# 220ACTo5VDC6AUSB_E3.net
KiCad netlist of a schematic drawn in Altium Designer
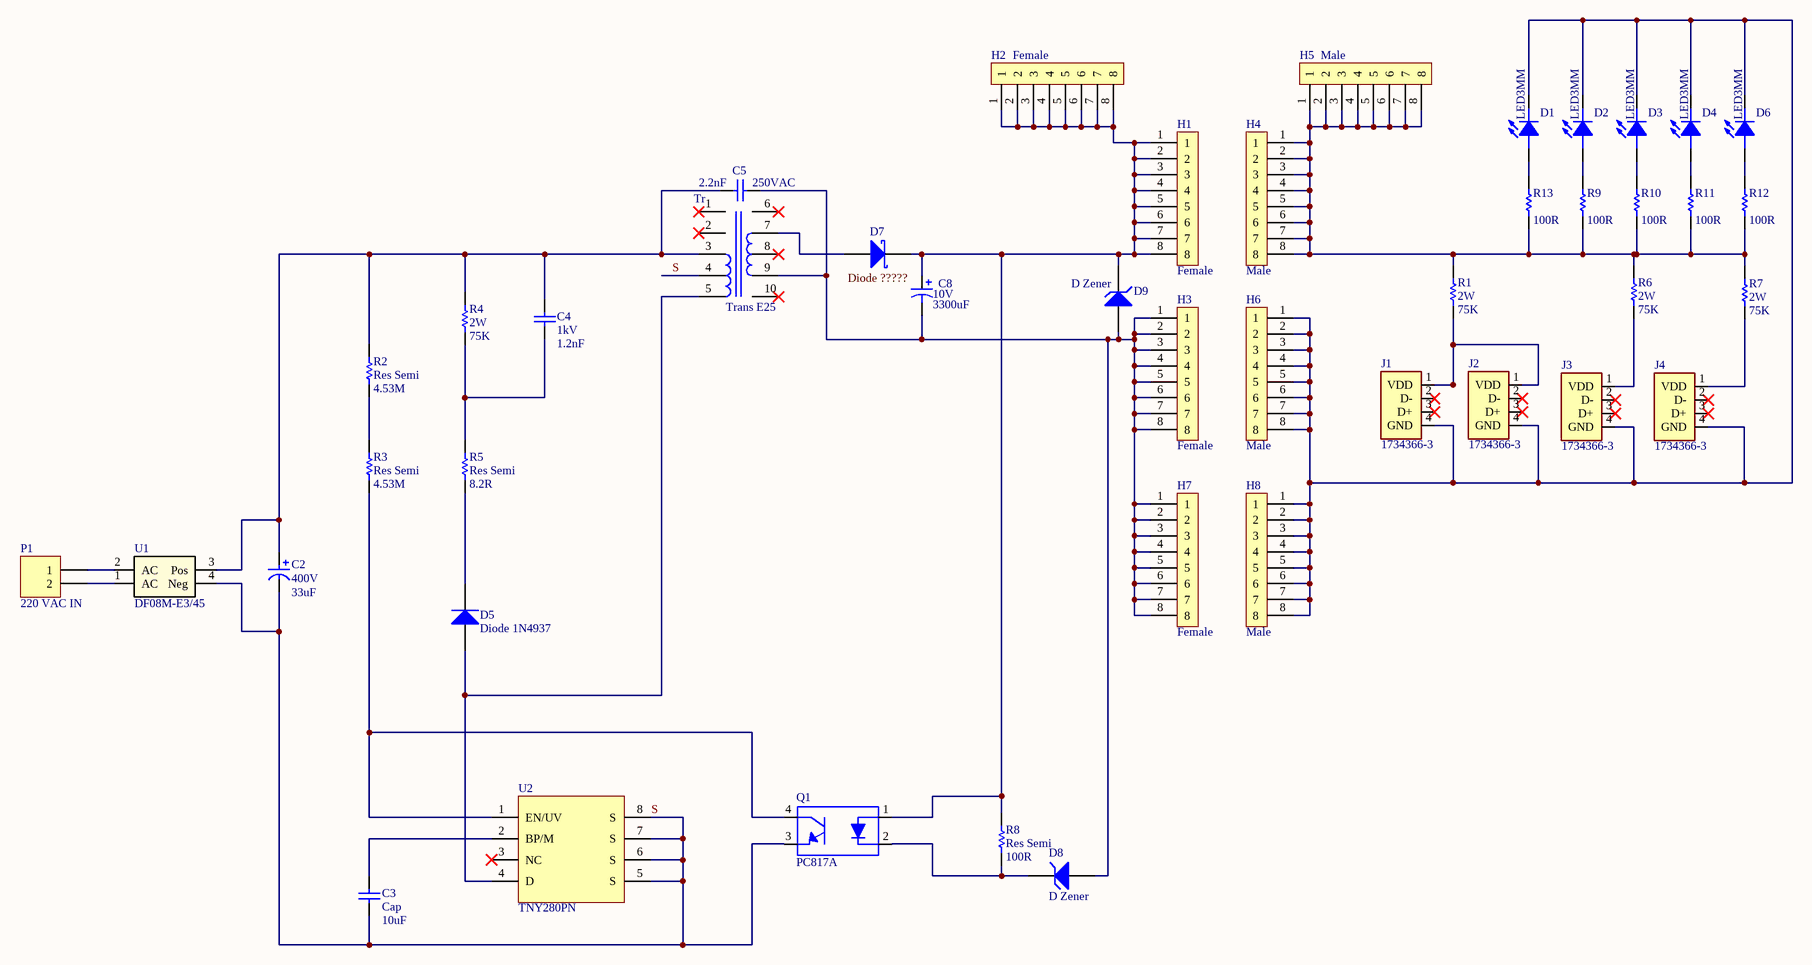
[diagram p0: 220ACTo5VDC6AUSB_E3.SchDoc]

(export (version "E")
  (design (tool "Eeschema 10.0.6"))
  (components
    (comp (ref "C2")
      (value "400V")
      (footprint "RB7.6_15_400v33uf - duplicate")
      (description "Polarized Capacitor (Radial)")
      (fields (field (name "ALTIUM_VALUE") "33uF") (field (name "PUBLISHER") "Altium Limited"))
      (libsource (lib "AC_DC_USB") (part "Cap Pol1"))
    )
    (comp (ref "C3")
      (value "Cap")
      (footprint "RAD-0.3_Ceramic_CAP")
      (description "Capacitor")
      (fields (field (name "16V") "10uF") (field (name "PUBLISHER") "Altium Limited"))
      (libsource (lib "Miscellaneous Devices") (part "Cap"))
    )
    (comp (ref "C4")
      (value "1kV")
      (footprint "RAD-0.3_Ceramic_CAP")
      (description "Capacitor")
      (fields (field (name "1KV") "1.2nF") (field (name "PUBLISHER") "Altium Limited"))
      (libsource (lib "Miscellaneous Devices") (part "Cap"))
    )
    (comp (ref "C5")
      (value "250VAC")
      (footprint "RAD-0.3_Ceramic_CAP")
      (description "Capacitor")
      (fields (field (name "250V") "2.2nF") (field (name "PUBLISHER") "Altium Limited"))
      (libsource (lib "Miscellaneous Devices") (part "Cap"))
    )
    (comp (ref "C8")
      (value "10V")
      (footprint "RB7.6_15_400v33uf")
      (description "Polarized Capacitor (Radial)")
      (fields (field (name "ALTIUM_VALUE") "3300uF") (field (name "PUBLISHER") "Altium Limited"))
      (libsource (lib "Miscellaneous Devices") (part "Cap Pol1"))
    )
    (comp (ref "D1")
      (value "LED3MM")
      (footprint "LED3mm_GREEN")
      (description "Light Emitting Diode")
      (fields (field (name "DESIGNER") "Ali Hafizi"))
      (libsource (lib "AC_DC_USB") (part "LED 3MM"))
    )
    (comp (ref "D2")
      (value "LED3MM")
      (footprint "LED3mm_GREEN")
      (description "Light Emitting Diode")
      (fields (field (name "DESIGNER") "Ali Hafizi"))
      (libsource (lib "AC_DC_USB") (part "LED 3MM"))
    )
    (comp (ref "D3")
      (value "LED3MM")
      (footprint "LED3mm_GREEN")
      (description "Light Emitting Diode")
      (fields (field (name "DESIGNER") "Ali Hafizi"))
      (libsource (lib "AC_DC_USB") (part "LED 3MM"))
    )
    (comp (ref "D4")
      (value "LED3MM")
      (footprint "LED3mm_GREEN")
      (description "Light Emitting Diode")
      (fields (field (name "DESIGNER") "Ali Hafizi"))
      (libsource (lib "AC_DC_USB") (part "LED 3MM"))
    )
    (comp (ref "D5")
      (value "Diode 1N4937")
      (footprint "DO-41_1N4006")
      (description "1 Amp General Purpose Rectifier")
      (fields (field (name "PUBLISHER") "Altium Limited"))
      (libsource (lib "Miscellaneous Devices") (part "Diode 1N4001"))
    )
    (comp (ref "D6")
      (value "LED3MM")
      (footprint "LED3mm_GREEN")
      (description "Light Emitting Diode")
      (fields (field (name "DESIGNER") "Ali Hafizi"))
      (libsource (lib "AC_DC_USB") (part "LED 3MM"))
    )
    (comp (ref "D7")
      (value "Diode ?????")
      (footprint "DO-41_1N4006")
      (description "Schottky Rectifier")
      (fields (field (name "PUBLISHER") "Altium Limited"))
      (libsource (lib "Miscellaneous Devices") (part "Diode 11DQ03"))
    )
    (comp (ref "D8")
      (value "D Zener")
      (footprint "DO-41_1N4006")
      (description "Zener Diode")
      (fields (field (name "PUBLISHER") "Altium Limited"))
      (libsource (lib "Miscellaneous Devices") (part "D Zener"))
    )
    (comp (ref "D9")
      (value "D Zener")
      (footprint "DO-41_1N4006")
      (description "Zener Diode")
      (fields (field (name "PUBLISHER") "Altium Limited"))
      (libsource (lib "Schlib1") (part "D Zener"))
    )
    (comp (ref "H1")
      (value "Female")
      (footprint "Header1X8 - female")
      (libsource (lib "") (part "Header-8Pin_1"))
    )
    (comp (ref "H2")
      (value "Female")
      (footprint "Header1X8 - female")
      (libsource (lib "") (part "Header-8Pin_2"))
    )
    (comp (ref "H3")
      (value "Female")
      (footprint "Header1X8 - female")
      (libsource (lib "") (part "Header-8Pin_1"))
    )
    (comp (ref "H4")
      (value "Male")
      (footprint "Header1X8 - male")
      (libsource (lib "AC_DC_USB") (part "Header-8Pin"))
    )
    (comp (ref "H5")
      (value "Male")
      (footprint "Header1X8 - male")
      (libsource (lib "") (part "Header-8Pin_2"))
    )
    (comp (ref "H6")
      (value "Male")
      (footprint "Header1X8 - male")
      (libsource (lib "AC_DC_USB") (part "Header-8Pin"))
    )
    (comp (ref "H7")
      (value "Female")
      (footprint "Header1X8 - female")
      (libsource (lib "") (part "Header-8Pin_1"))
    )
    (comp (ref "H8")
      (value "Male")
      (footprint "Header1X8 - male")
      (libsource (lib "AC_DC_USB") (part "Header-8Pin"))
    )
    (comp (ref "J1")
      (value "1734366-3")
      (footprint "USB_Vertical")
      (description "Conn USB 2.0 Type A RCP 4 POS Solder ST Thru-Hole 4 Terminal 1 Port Box/Tray")
      (fields (field (name "MF") "TE Connectivity"))
      (libsource (lib "1734366-3") (part "1734366-3"))
    )
    (comp (ref "J2")
      (value "1734366-3")
      (footprint "USB_Vertical")
      (description "Conn USB 2.0 Type A RCP 4 POS Solder ST Thru-Hole 4 Terminal 1 Port Box/Tray")
      (fields (field (name "MF") "TE Connectivity"))
      (libsource (lib "1734366-3") (part "1734366-3"))
    )
    (comp (ref "J3")
      (value "1734366-3")
      (footprint "USB_Vertical")
      (description "Conn USB 2.0 Type A RCP 4 POS Solder ST Thru-Hole 4 Terminal 1 Port Box/Tray")
      (fields (field (name "MF") "TE Connectivity"))
      (libsource (lib "1734366-3") (part "1734366-3"))
    )
    (comp (ref "J4")
      (value "1734366-3")
      (footprint "USB_Vertical")
      (description "Conn USB 2.0 Type A RCP 4 POS Solder ST Thru-Hole 4 Terminal 1 Port Box/Tray")
      (fields (field (name "MF") "TE Connectivity"))
      (libsource (lib "1734366-3") (part "1734366-3"))
    )
    (comp (ref "P1")
      (value "220 VAC IN")
      (footprint "HDR1X2")
      (description "Header, 2-Pin")
      (fields (field (name "PUBLISHER") "Altium Limited"))
      (libsource (lib "Miscellaneous Connectors") (part "Header 2"))
    )
    (comp (ref "Q1")
      (value "PC817A")
      (footprint "PC817 Dip")
      (description "Optoisolator Transistor Output 5000Vrms 1 Channel 4-DIP")
      (fields (field (name "MF") "Taiwan Semiconductor"))
      (libsource (lib "SnapEDAsch") (part "PC817A"))
    )
    (comp (ref "R1")
      (value "2W")
      (footprint "AXIAL-0.5_Res")
      (description "Semiconductor Resistor")
      (fields (field (name "2W") "75K") (field (name "PUBLISHER") "Altium Limited"))
      (libsource (lib "Miscellaneous Devices") (part "Res Semi"))
    )
    (comp (ref "R2")
      (value "Res Semi")
      (footprint "AXIAL-0.5_Res")
      (description "Semiconductor Resistor")
      (fields (field (name "ALTIUM_VALUE") "4.53M") (field (name "PUBLISHER") "Altium Limited"))
      (libsource (lib "Miscellaneous Devices") (part "Res Semi"))
    )
    (comp (ref "R3")
      (value "Res Semi")
      (footprint "AXIAL-0.5_Res")
      (description "Semiconductor Resistor")
      (fields (field (name "ALTIUM_VALUE") "4.53M") (field (name "PUBLISHER") "Altium Limited"))
      (libsource (lib "Miscellaneous Devices") (part "Res Semi"))
    )
    (comp (ref "R4")
      (value "2W")
      (footprint "AXIAL-0.5_Res")
      (description "Semiconductor Resistor")
      (fields (field (name "2W") "75K") (field (name "PUBLISHER") "Altium Limited"))
      (libsource (lib "Miscellaneous Devices") (part "Res Semi"))
    )
    (comp (ref "R5")
      (value "Res Semi")
      (footprint "AXIAL-0.5_Res")
      (description "Semiconductor Resistor")
      (fields (field (name "ALTIUM_VALUE") "8.2R") (field (name "PUBLISHER") "Altium Limited"))
      (libsource (lib "Miscellaneous Devices") (part "Res Semi"))
    )
    (comp (ref "R6")
      (value "2W")
      (footprint "AXIAL-0.5_Res")
      (description "Semiconductor Resistor")
      (fields (field (name "2W") "75K") (field (name "PUBLISHER") "Altium Limited"))
      (libsource (lib "Miscellaneous Devices") (part "Res Semi"))
    )
    (comp (ref "R7")
      (value "2W")
      (footprint "AXIAL-0.5_Res")
      (description "Semiconductor Resistor")
      (fields (field (name "2W") "75K") (field (name "PUBLISHER") "Altium Limited"))
      (libsource (lib "Miscellaneous Devices") (part "Res Semi"))
    )
    (comp (ref "R8")
      (value "Res Semi")
      (footprint "AXIAL-0.5_Res")
      (description "Semiconductor Resistor")
      (fields (field (name "ALTIUM_VALUE") "100R") (field (name "PUBLISHER") "Altium Limited"))
      (libsource (lib "Miscellaneous Devices") (part "Res Semi"))
    )
    (comp (ref "R9")
      (value "100R")
      (footprint "AXIAL-0.5_Res")
      (description "Semiconductor Resistor")
      (fields (field (name "Comment") "Res Semi") (field (name "PUBLISHER") "Altium Limited"))
      (libsource (lib "Miscellaneous Devices") (part "Res Semi"))
    )
    (comp (ref "R10")
      (value "100R")
      (footprint "AXIAL-0.5_Res")
      (description "Semiconductor Resistor")
      (fields (field (name "Comment") "Res Semi") (field (name "PUBLISHER") "Altium Limited"))
      (libsource (lib "Miscellaneous Devices") (part "Res Semi"))
    )
    (comp (ref "R11")
      (value "100R")
      (footprint "AXIAL-0.5_Res")
      (description "Semiconductor Resistor")
      (fields (field (name "Comment") "Res Semi") (field (name "PUBLISHER") "Altium Limited"))
      (libsource (lib "Miscellaneous Devices") (part "Res Semi"))
    )
    (comp (ref "R12")
      (value "100R")
      (footprint "AXIAL-0.5_Res")
      (description "Semiconductor Resistor")
      (fields (field (name "Comment") "Res Semi") (field (name "PUBLISHER") "Altium Limited"))
      (libsource (lib "Miscellaneous Devices") (part "Res Semi"))
    )
    (comp (ref "R13")
      (value "100R")
      (footprint "AXIAL-0.5_Res")
      (description "Semiconductor Resistor")
      (fields (field (name "Comment") "Res Semi") (field (name "PUBLISHER") "Altium Limited"))
      (libsource (lib "Miscellaneous Devices") (part "Res Semi"))
    )
    (comp (ref "Tr") (value "Trans E25") (footprint "Trans") (libsource (lib "AC_DC_USB") (part "Trans E25")))
    (comp (ref "U1")
      (value "DF08M-E3/45")
      (footprint "DF08M")
      (fields (field (name "COPYRIGHT") "Copyright (C) 2018 Accelerated Designs. All rights reserved"))
      (libsource (lib "AC_DC_USB") (part "DF08M-E3/45"))
    )
    (comp (ref "U2")
      (value "TNY280PN")
      (footprint "DIP762W46P254L988H533Q8")
      (description "Dip")
      (libsource (lib "Schlib1") (part "TNY280PN"))
    )
  )
  (nets
    (net (code "1") (name "/S") (class "Default")
      (node (ref "C2") (pin "2") (pinfunction "2_2") (pintype "passive"))
      (node (ref "C3") (pin "1") (pinfunction "1_1") (pintype "passive"))
      (node (ref "Q1") (pin "3") (pinfunction "3_3") (pintype "passive"))
      (node (ref "Tr") (pin "4") (pintype "passive"))
      (node (ref "U1") (pin "4") (pinfunction "Neg_4") (pintype "passive"))
      (node (ref "U2") (pin "5") (pinfunction "S_5") (pintype "passive"))
      (node (ref "U2") (pin "6") (pinfunction "S_6") (pintype "passive"))
      (node (ref "U2") (pin "7") (pinfunction "S_7") (pintype "passive"))
      (node (ref "U2") (pin "8") (pinfunction "S_8") (pintype "passive"))
    )
    (net (code "2") (name "Net-(C4-Pad1)") (class "Default")
      (node (ref "C4") (pin "1") (pinfunction "1_1") (pintype "passive"))
      (node (ref "R4") (pin "1") (pinfunction "1_1") (pintype "passive"))
      (node (ref "R5") (pin "2") (pinfunction "2_2") (pintype "passive"))
    )
    (net (code "3") (name "Net-(D1-ANODE)") (class "Default")
      (node (ref "D1") (pin "1") (pinfunction "ANODE_1") (pintype "passive"))
      (node (ref "R13") (pin "2") (pinfunction "2_2") (pintype "passive"))
    )
    (net (code "4") (name "Net-(D1-CATHODE)") (class "Default")
      (node (ref "D1") (pin "2") (pinfunction "CATHODE_2") (pintype "passive"))
      (node (ref "D2") (pin "2") (pinfunction "CATHODE_2") (pintype "passive"))
      (node (ref "D3") (pin "2") (pinfunction "CATHODE_2") (pintype "passive"))
      (node (ref "D4") (pin "2") (pinfunction "CATHODE_2") (pintype "passive"))
      (node (ref "D6") (pin "2") (pinfunction "CATHODE_2") (pintype "passive"))
      (node (ref "H6") (pin "1") (pinfunction "1_1") (pintype "passive"))
      (node (ref "H6") (pin "2") (pinfunction "2_2") (pintype "passive"))
      (node (ref "H6") (pin "3") (pinfunction "3_3") (pintype "passive"))
      (node (ref "H6") (pin "4") (pinfunction "4_4") (pintype "passive"))
      (node (ref "H6") (pin "5") (pinfunction "5_5") (pintype "passive"))
      (node (ref "H6") (pin "6") (pinfunction "6_6") (pintype "passive"))
      (node (ref "H6") (pin "7") (pinfunction "7_7") (pintype "passive"))
      (node (ref "H6") (pin "8") (pinfunction "8_8") (pintype "passive"))
      (node (ref "H8") (pin "1") (pinfunction "1_1") (pintype "passive"))
      (node (ref "H8") (pin "2") (pinfunction "2_2") (pintype "passive"))
      (node (ref "H8") (pin "3") (pinfunction "3_3") (pintype "passive"))
      (node (ref "H8") (pin "4") (pinfunction "4_4") (pintype "passive"))
      (node (ref "H8") (pin "5") (pinfunction "5_5") (pintype "passive"))
      (node (ref "H8") (pin "6") (pinfunction "6_6") (pintype "passive"))
      (node (ref "H8") (pin "7") (pinfunction "7_7") (pintype "passive"))
      (node (ref "H8") (pin "8") (pinfunction "8_8") (pintype "passive"))
      (node (ref "J1") (pin "4") (pinfunction "GND_4") (pintype "power_in"))
      (node (ref "J2") (pin "4") (pinfunction "GND_4") (pintype "power_in"))
      (node (ref "J3") (pin "4") (pinfunction "GND_4") (pintype "power_in"))
      (node (ref "J4") (pin "4") (pinfunction "GND_4") (pintype "power_in"))
    )
    (net (code "5") (name "Net-(D2-ANODE)") (class "Default")
      (node (ref "D2") (pin "1") (pinfunction "ANODE_1") (pintype "passive"))
      (node (ref "R9") (pin "2") (pinfunction "2_2") (pintype "passive"))
    )
    (net (code "6") (name "Net-(D3-ANODE)") (class "Default")
      (node (ref "D3") (pin "1") (pinfunction "ANODE_1") (pintype "passive"))
      (node (ref "R10") (pin "2") (pinfunction "2_2") (pintype "passive"))
    )
    (net (code "7") (name "Net-(D4-ANODE)") (class "Default")
      (node (ref "D4") (pin "1") (pinfunction "ANODE_1") (pintype "passive"))
      (node (ref "R11") (pin "2") (pinfunction "2_2") (pintype "passive"))
    )
    (net (code "8") (name "Net-(D5-A)") (class "Default")
      (node (ref "D5") (pin "1") (pinfunction "A_1") (pintype "passive"))
      (node (ref "Tr") (pin "5") (pintype "passive"))
      (node (ref "U2") (pin "4") (pinfunction "D_4") (pintype "passive"))
    )
    (net (code "9") (name "Net-(D5-K)") (class "Default")
      (node (ref "D5") (pin "2") (pinfunction "K_2") (pintype "passive"))
      (node (ref "R5") (pin "1") (pinfunction "1_1") (pintype "passive"))
    )
    (net (code "10") (name "Net-(D6-ANODE)") (class "Default")
      (node (ref "D6") (pin "1") (pinfunction "ANODE_1") (pintype "passive"))
      (node (ref "R12") (pin "2") (pinfunction "2_2") (pintype "passive"))
    )
    (net (code "11") (name "Net-(D7-A)") (class "Default")
      (node (ref "D7") (pin "1") (pinfunction "A_1") (pintype "passive"))
      (node (ref "Tr") (pin "7") (pintype "passive"))
    )
    (net (code "12") (name "Net-(D7-K)") (class "Default")
      (node (ref "C8") (pin "1") (pinfunction "1_1") (pintype "passive"))
      (node (ref "D7") (pin "2") (pinfunction "K_2") (pintype "passive"))
      (node (ref "D9") (pin "2") (pinfunction "2_2") (pintype "passive"))
      (node (ref "H1") (pin "1") (pinfunction "1_1") (pintype "passive"))
      (node (ref "H1") (pin "2") (pinfunction "2_2") (pintype "passive"))
      (node (ref "H1") (pin "3") (pinfunction "3_3") (pintype "passive"))
      (node (ref "H1") (pin "4") (pinfunction "4_4") (pintype "passive"))
      (node (ref "H1") (pin "5") (pinfunction "5_5") (pintype "passive"))
      (node (ref "H1") (pin "6") (pinfunction "6_6") (pintype "passive"))
      (node (ref "H1") (pin "7") (pinfunction "7_7") (pintype "passive"))
      (node (ref "H1") (pin "8") (pinfunction "8_8") (pintype "passive"))
      (node (ref "H2") (pin "1") (pinfunction "1_1") (pintype "passive"))
      (node (ref "H2") (pin "2") (pinfunction "2_2") (pintype "passive"))
      (node (ref "H2") (pin "3") (pinfunction "3_3") (pintype "passive"))
      (node (ref "H2") (pin "4") (pinfunction "4_4") (pintype "passive"))
      (node (ref "H2") (pin "5") (pinfunction "5_5") (pintype "passive"))
      (node (ref "H2") (pin "6") (pinfunction "6_6") (pintype "passive"))
      (node (ref "H2") (pin "7") (pinfunction "7_7") (pintype "passive"))
      (node (ref "H2") (pin "8") (pinfunction "8_8") (pintype "passive"))
      (node (ref "Q1") (pin "1") (pinfunction "1_1") (pintype "passive"))
      (node (ref "R8") (pin "2") (pinfunction "2_2") (pintype "passive"))
    )
    (net (code "13") (name "Net-(D8-A)") (class "Default")
      (node (ref "C5") (pin "1") (pinfunction "1_1") (pintype "passive"))
      (node (ref "C8") (pin "2") (pinfunction "2_2") (pintype "passive"))
      (node (ref "D8") (pin "1") (pinfunction "A_1") (pintype "passive"))
      (node (ref "D9") (pin "1") (pinfunction "1_1") (pintype "passive"))
      (node (ref "H3") (pin "1") (pinfunction "1_1") (pintype "passive"))
      (node (ref "H3") (pin "2") (pinfunction "2_2") (pintype "passive"))
      (node (ref "H3") (pin "3") (pinfunction "3_3") (pintype "passive"))
      (node (ref "H3") (pin "4") (pinfunction "4_4") (pintype "passive"))
      (node (ref "H3") (pin "5") (pinfunction "5_5") (pintype "passive"))
      (node (ref "H3") (pin "6") (pinfunction "6_6") (pintype "passive"))
      (node (ref "H3") (pin "7") (pinfunction "7_7") (pintype "passive"))
      (node (ref "H3") (pin "8") (pinfunction "8_8") (pintype "passive"))
      (node (ref "H7") (pin "1") (pinfunction "1_1") (pintype "passive"))
      (node (ref "H7") (pin "2") (pinfunction "2_2") (pintype "passive"))
      (node (ref "H7") (pin "3") (pinfunction "3_3") (pintype "passive"))
      (node (ref "H7") (pin "4") (pinfunction "4_4") (pintype "passive"))
      (node (ref "H7") (pin "5") (pinfunction "5_5") (pintype "passive"))
      (node (ref "H7") (pin "6") (pinfunction "6_6") (pintype "passive"))
      (node (ref "H7") (pin "7") (pinfunction "7_7") (pintype "passive"))
      (node (ref "H7") (pin "8") (pinfunction "8_8") (pintype "passive"))
      (node (ref "Tr") (pin "9") (pintype "passive"))
    )
    (net (code "14") (name "Net-(D8-K)") (class "Default")
      (node (ref "D8") (pin "2") (pinfunction "K_2") (pintype "passive"))
      (node (ref "Q1") (pin "2") (pinfunction "2_2") (pintype "passive"))
      (node (ref "R8") (pin "1") (pinfunction "1_1") (pintype "passive"))
    )
    (net (code "15") (name "Net-(H4-Pad1)") (class "Default")
      (node (ref "H4") (pin "1") (pinfunction "1_1") (pintype "passive"))
      (node (ref "H4") (pin "2") (pinfunction "2_2") (pintype "passive"))
      (node (ref "H4") (pin "3") (pinfunction "3_3") (pintype "passive"))
      (node (ref "H4") (pin "4") (pinfunction "4_4") (pintype "passive"))
      (node (ref "H4") (pin "5") (pinfunction "5_5") (pintype "passive"))
      (node (ref "H4") (pin "6") (pinfunction "6_6") (pintype "passive"))
      (node (ref "H4") (pin "7") (pinfunction "7_7") (pintype "passive"))
      (node (ref "H4") (pin "8") (pinfunction "8_8") (pintype "passive"))
      (node (ref "H5") (pin "1") (pinfunction "1_1") (pintype "passive"))
      (node (ref "H5") (pin "2") (pinfunction "2_2") (pintype "passive"))
      (node (ref "H5") (pin "3") (pinfunction "3_3") (pintype "passive"))
      (node (ref "H5") (pin "4") (pinfunction "4_4") (pintype "passive"))
      (node (ref "H5") (pin "5") (pinfunction "5_5") (pintype "passive"))
      (node (ref "H5") (pin "6") (pinfunction "6_6") (pintype "passive"))
      (node (ref "H5") (pin "7") (pinfunction "7_7") (pintype "passive"))
      (node (ref "H5") (pin "8") (pinfunction "8_8") (pintype "passive"))
      (node (ref "R1") (pin "2") (pinfunction "2_2") (pintype "passive"))
      (node (ref "R10") (pin "1") (pinfunction "1_1") (pintype "passive"))
      (node (ref "R11") (pin "1") (pinfunction "1_1") (pintype "passive"))
      (node (ref "R12") (pin "1") (pinfunction "1_1") (pintype "passive"))
      (node (ref "R13") (pin "1") (pinfunction "1_1") (pintype "passive"))
      (node (ref "R6") (pin "2") (pinfunction "2_2") (pintype "passive"))
      (node (ref "R7") (pin "2") (pinfunction "2_2") (pintype "passive"))
      (node (ref "R9") (pin "1") (pinfunction "1_1") (pintype "passive"))
    )
    (net (code "16") (name "Net-(J1-VDD)") (class "Default")
      (node (ref "J1") (pin "1") (pinfunction "VDD_1") (pintype "power_in"))
      (node (ref "J2") (pin "1") (pinfunction "VDD_1") (pintype "power_in"))
      (node (ref "R1") (pin "1") (pinfunction "1_1") (pintype "passive"))
    )
    (net (code "17") (name "Net-(J3-VDD)") (class "Default")
      (node (ref "J3") (pin "1") (pinfunction "VDD_1") (pintype "power_in"))
      (node (ref "R6") (pin "1") (pinfunction "1_1") (pintype "passive"))
    )
    (net (code "18") (name "Net-(J4-VDD)") (class "Default")
      (node (ref "J4") (pin "1") (pinfunction "VDD_1") (pintype "power_in"))
      (node (ref "R7") (pin "1") (pinfunction "1_1") (pintype "passive"))
    )
    (net (code "19") (name "Net-(P1-Pad1)") (class "Default")
      (node (ref "P1") (pin "1") (pinfunction "1_1") (pintype "passive"))
      (node (ref "U1") (pin "2") (pinfunction "AC_2") (pintype "passive"))
    )
    (net (code "20") (name "Net-(P1-Pad2)") (class "Default")
      (node (ref "P1") (pin "2") (pinfunction "2_2") (pintype "passive"))
      (node (ref "U1") (pin "1") (pinfunction "AC_1") (pintype "passive"))
    )
    (net (code "21") (name "Net-(R2-Pad1)") (class "Default")
      (node (ref "R2") (pin "1") (pinfunction "1_1") (pintype "passive"))
      (node (ref "R3") (pin "2") (pinfunction "2_2") (pintype "passive"))
    )
    (net (code "22") (name "Net-(U1-Pos)") (class "Default")
      (node (ref "C2") (pin "1") (pinfunction "1_1") (pintype "passive"))
      (node (ref "C4") (pin "2") (pinfunction "2_2") (pintype "passive"))
      (node (ref "C5") (pin "2") (pinfunction "2_2") (pintype "passive"))
      (node (ref "R2") (pin "2") (pinfunction "2_2") (pintype "passive"))
      (node (ref "R4") (pin "2") (pinfunction "2_2") (pintype "passive"))
      (node (ref "Tr") (pin "3") (pintype "passive"))
      (node (ref "U1") (pin "3") (pinfunction "Pos_3") (pintype "passive"))
    )
    (net (code "23") (name "Net-(U2-BP{slash}M)") (class "Default")
      (node (ref "C3") (pin "2") (pinfunction "2_2") (pintype "passive"))
      (node (ref "U2") (pin "2") (pinfunction "BP/M_2") (pintype "passive"))
    )
    (net (code "24") (name "Net-(U2-EN{slash}UV)") (class "Default")
      (node (ref "Q1") (pin "4") (pinfunction "4_4") (pintype "passive"))
      (node (ref "R3") (pin "1") (pinfunction "1_1") (pintype "passive"))
      (node (ref "U2") (pin "1") (pinfunction "EN/UV_1") (pintype "passive"))
    )
    (net (code "25") (name "unconnected-(J1-D+-Pad3)") (class "Default")
      (node (ref "J1") (pin "3") (pinfunction "D+_3") (pintype "bidirectional+no_connect"))
    )
    (net (code "26") (name "unconnected-(J1-D--Pad2)") (class "Default")
      (node (ref "J1") (pin "2") (pinfunction "D-_2") (pintype "bidirectional+no_connect"))
    )
    (net (code "27") (name "unconnected-(J2-D+-Pad3)") (class "Default")
      (node (ref "J2") (pin "3") (pinfunction "D+_3") (pintype "bidirectional+no_connect"))
    )
    (net (code "28") (name "unconnected-(J2-D--Pad2)") (class "Default")
      (node (ref "J2") (pin "2") (pinfunction "D-_2") (pintype "bidirectional+no_connect"))
    )
    (net (code "29") (name "unconnected-(J3-D+-Pad3)") (class "Default")
      (node (ref "J3") (pin "3") (pinfunction "D+_3") (pintype "bidirectional+no_connect"))
    )
    (net (code "30") (name "unconnected-(J3-D--Pad2)") (class "Default")
      (node (ref "J3") (pin "2") (pinfunction "D-_2") (pintype "bidirectional+no_connect"))
    )
    (net (code "31") (name "unconnected-(J4-D+-Pad3)") (class "Default")
      (node (ref "J4") (pin "3") (pinfunction "D+_3") (pintype "bidirectional+no_connect"))
    )
    (net (code "32") (name "unconnected-(J4-D--Pad2)") (class "Default")
      (node (ref "J4") (pin "2") (pinfunction "D-_2") (pintype "bidirectional+no_connect"))
    )
    (net (code "33") (name "unconnected-(Tr-Pad1)") (class "Default")
      (node (ref "Tr") (pin "1") (pinfunction "1_1") (pintype "passive+no_connect"))
    )
    (net (code "34") (name "unconnected-(Tr-Pad2)") (class "Default")
      (node (ref "Tr") (pin "2") (pinfunction "2_2") (pintype "passive+no_connect"))
    )
    (net (code "35") (name "unconnected-(Tr-Pad6)") (class "Default")
      (node (ref "Tr") (pin "6") (pinfunction "6_6") (pintype "passive+no_connect"))
    )
    (net (code "36") (name "unconnected-(Tr-Pad8)") (class "Default")
      (node (ref "Tr") (pin "8") (pinfunction "8_8") (pintype "passive+no_connect"))
    )
    (net (code "37") (name "unconnected-(Tr-Pad10)") (class "Default")
      (node (ref "Tr") (pin "10") (pinfunction "10_10") (pintype "passive+no_connect"))
    )
    (net (code "38") (name "unconnected-(U2-NC-Pad3)") (class "Default")
      (node (ref "U2") (pin "3") (pinfunction "NC_3") (pintype "passive+no_connect"))
    )
  )
)
